# linistep1mod.net
KiCad netlist of a schematic drawn in EAGLE
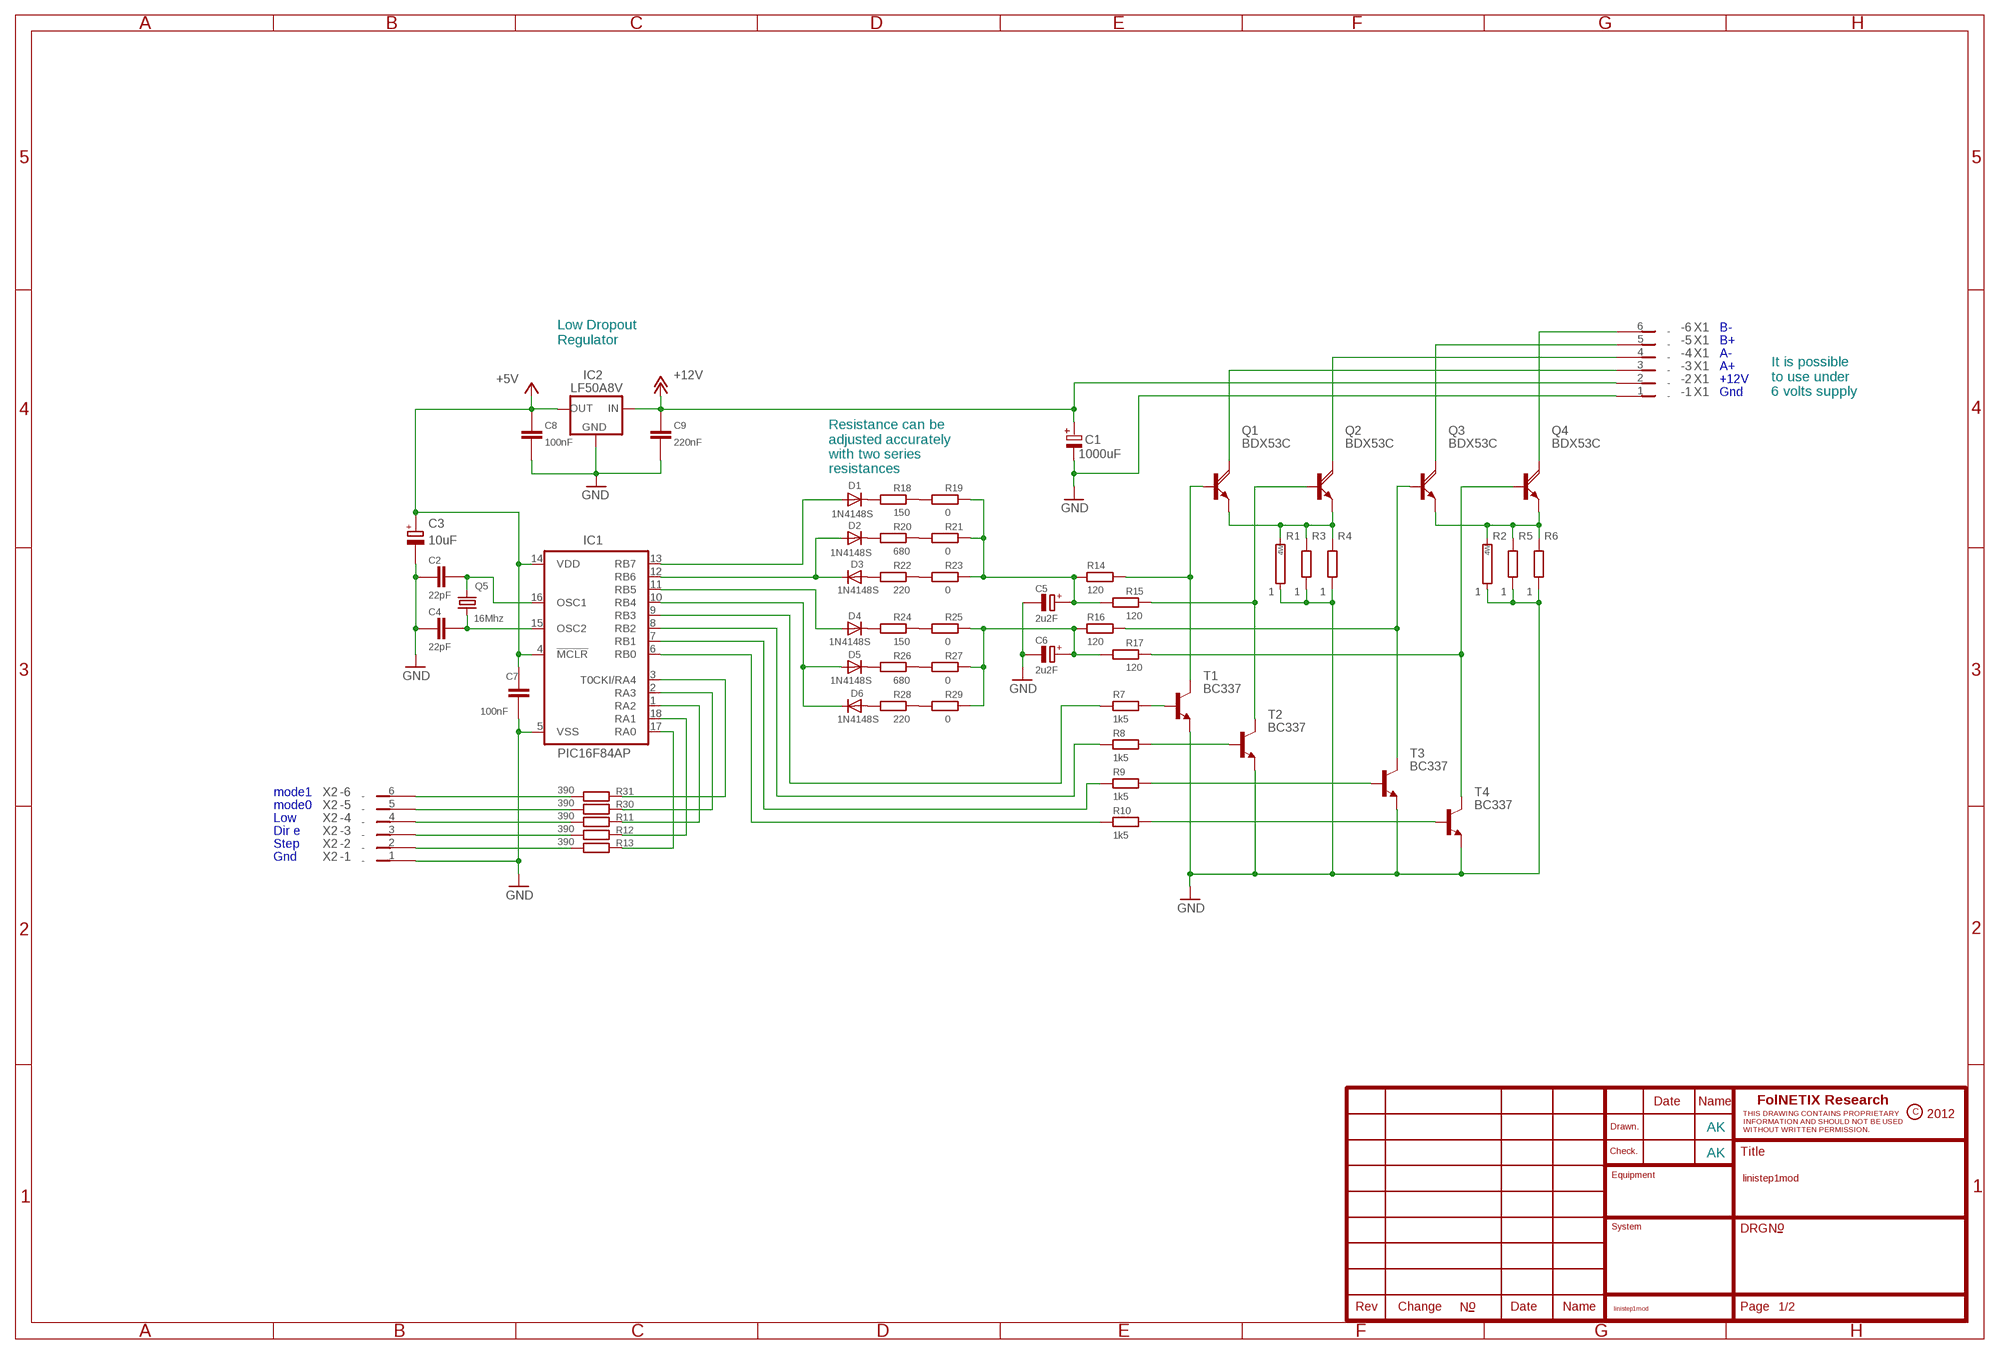
[diagram p0: schematic, sheet 1]
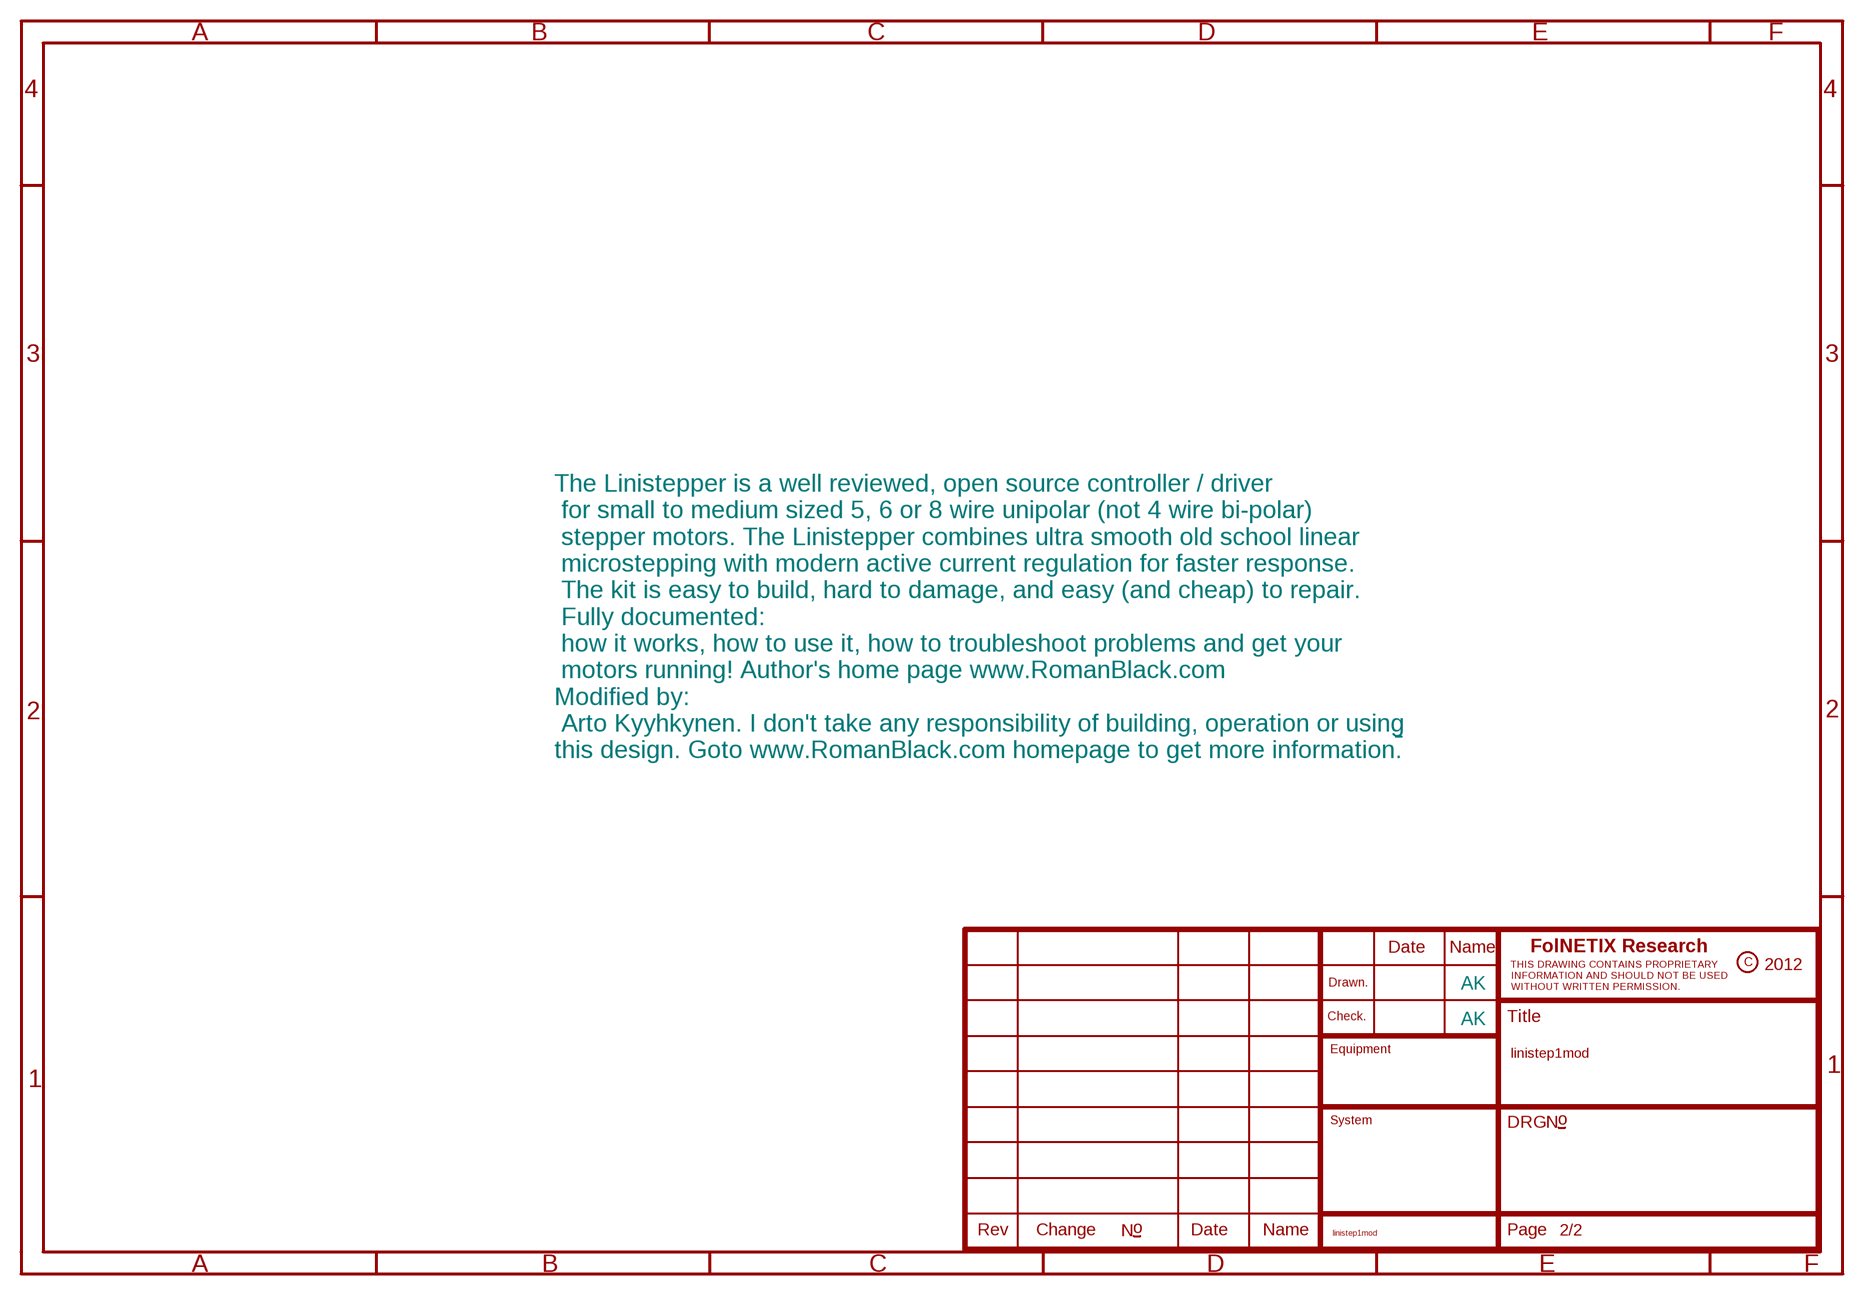
[diagram p1: schematic, sheet 2]

(export (version "E")
  (design (tool "Eeschema 10.0.6"))
  (components
    (comp (ref "C1")
      (value "1000uF")
      (footprint "eagle-import:E5-10,5")
      (libsource (lib "eagle-import") (part "E5-10,5"))
    )
    (comp (ref "C2")
      (value "22pF")
      (footprint "eagle-import:CAPC2012X145AN")
      (libsource (lib "eagle-import") (part "CAPACITOR_0805"))
    )
    (comp (ref "C3")
      (value "10uF")
      (footprint "eagle-import:CAPMP3528X210N")
      (libsource (lib "eagle-import") (part "POLARISED_B_CASE"))
    )
    (comp (ref "C4")
      (value "22pF")
      (footprint "eagle-import:CAPC2012X145AN")
      (libsource (lib "eagle-import") (part "CAPACITOR_0805"))
    )
    (comp (ref "C5")
      (value "2u2F")
      (footprint "eagle-import:CAPMP3216X180N")
      (libsource (lib "eagle-import") (part "POLARISED_A_CASE"))
    )
    (comp (ref "C6")
      (value "2u2F")
      (footprint "eagle-import:CAPMP3216X180N")
      (libsource (lib "eagle-import") (part "POLARISED_A_CASE"))
    )
    (comp (ref "C7")
      (value "100nF")
      (footprint "eagle-import:CAPC2012X145AN")
      (libsource (lib "eagle-import") (part "CAPACITOR_0805"))
    )
    (comp (ref "C8")
      (value "100nF")
      (footprint "eagle-import:CAPC2012X145AN")
      (libsource (lib "eagle-import") (part "CAPACITOR_0805"))
    )
    (comp (ref "C9")
      (value "220nF")
      (footprint "eagle-import:CAPC3225X168N")
      (libsource (lib "eagle-import") (part "CAPACITOR_1210"))
    )
    (comp (ref "D1")
      (value "1N4148S")
      (footprint "eagle-import:DO35-7A")
      (libsource (lib "eagle-import") (part "1N4148S"))
    )
    (comp (ref "D2")
      (value "1N4148S")
      (footprint "eagle-import:DO35-7A")
      (libsource (lib "eagle-import") (part "1N4148S"))
    )
    (comp (ref "D3")
      (value "1N4148S")
      (footprint "eagle-import:DO35-7A")
      (libsource (lib "eagle-import") (part "1N4148S"))
    )
    (comp (ref "D4")
      (value "1N4148S")
      (footprint "eagle-import:DO35-7A")
      (libsource (lib "eagle-import") (part "1N4148S"))
    )
    (comp (ref "D5")
      (value "1N4148S")
      (footprint "eagle-import:DO35-7A")
      (libsource (lib "eagle-import") (part "1N4148S"))
    )
    (comp (ref "D6")
      (value "1N4148S")
      (footprint "eagle-import:DO35-7A")
      (libsource (lib "eagle-import") (part "1N4148S"))
    )
    (comp (ref "IC1")
      (value "PIC16F84AP")
      (footprint "eagle-import:DIL18")
      (libsource (lib "eagle-import") (part "PIC16F8P4A"))
    )
    (comp (ref "IC2")
      (value "LF50A8V")
      (footprint "eagle-import:78XXL")
      (libsource (lib "eagle-import") (part "78XXL"))
    )
    (comp (ref "Q1")
      (value "BDX53C")
      (footprint "eagle-import:TO220AHS")
      (libsource (lib "eagle-import") (part "TIP120S"))
    )
    (comp (ref "Q2")
      (value "BDX53C")
      (footprint "eagle-import:TO220AHS")
      (libsource (lib "eagle-import") (part "TIP120S"))
    )
    (comp (ref "Q3")
      (value "BDX53C")
      (footprint "eagle-import:TO220AHS")
      (libsource (lib "eagle-import") (part "TIP120S"))
    )
    (comp (ref "Q4")
      (value "BDX53C")
      (footprint "eagle-import:TO220AHS")
      (libsource (lib "eagle-import") (part "TIP120S"))
    )
    (comp (ref "Q5")
      (value "16Mhz")
      (footprint "eagle-import:HC49_S")
      (libsource (lib "eagle-import") (part "HC49/S"))
    )
    (comp (ref "R1")
      (value "1")
      (footprint "eagle-import:206A")
      (libsource (lib "eagle-import") (part "206A"))
    )
    (comp (ref "R2")
      (value "1")
      (footprint "eagle-import:206A")
      (libsource (lib "eagle-import") (part "206A"))
    )
    (comp (ref "R3")
      (value "1")
      (footprint "eagle-import:0411_12")
      (libsource (lib "eagle-import") (part "0411/12"))
    )
    (comp (ref "R4")
      (value "1")
      (footprint "eagle-import:0411_12")
      (libsource (lib "eagle-import") (part "0411/12"))
    )
    (comp (ref "R5")
      (value "1")
      (footprint "eagle-import:0411_12")
      (libsource (lib "eagle-import") (part "0411/12"))
    )
    (comp (ref "R6")
      (value "1")
      (footprint "eagle-import:0411_12")
      (libsource (lib "eagle-import") (part "0411/12"))
    )
    (comp (ref "R7")
      (value "1k5")
      (footprint "eagle-import:RESC3115X70N")
      (libsource (lib "eagle-import") (part "RESISTOR_1206"))
    )
    (comp (ref "R8")
      (value "1k5")
      (footprint "eagle-import:RESC3115X70N")
      (libsource (lib "eagle-import") (part "RESISTOR_1206"))
    )
    (comp (ref "R9")
      (value "1k5")
      (footprint "eagle-import:RESC3115X70N")
      (libsource (lib "eagle-import") (part "RESISTOR_1206"))
    )
    (comp (ref "R10")
      (value "1k5")
      (footprint "eagle-import:RESC3115X70N")
      (libsource (lib "eagle-import") (part "RESISTOR_1206"))
    )
    (comp (ref "R11")
      (value "390")
      (footprint "eagle-import:RESC3115X70N")
      (libsource (lib "eagle-import") (part "RESISTOR_1206"))
    )
    (comp (ref "R12")
      (value "390")
      (footprint "eagle-import:RESC3115X70N")
      (libsource (lib "eagle-import") (part "RESISTOR_1206"))
    )
    (comp (ref "R13")
      (value "390")
      (footprint "eagle-import:RESC3115X70N")
      (libsource (lib "eagle-import") (part "RESISTOR_1206"))
    )
    (comp (ref "R14")
      (value "120")
      (footprint "eagle-import:RESC3115X70N")
      (libsource (lib "eagle-import") (part "RESISTOR_1206"))
    )
    (comp (ref "R15")
      (value "120")
      (footprint "eagle-import:RESC3115X70N")
      (libsource (lib "eagle-import") (part "RESISTOR_1206"))
    )
    (comp (ref "R16")
      (value "120")
      (footprint "eagle-import:RESC3115X70N")
      (libsource (lib "eagle-import") (part "RESISTOR_1206"))
    )
    (comp (ref "R17")
      (value "120")
      (footprint "eagle-import:RESC3115X70N")
      (libsource (lib "eagle-import") (part "RESISTOR_1206"))
    )
    (comp (ref "R18")
      (value "150")
      (footprint "eagle-import:RESC3115X70N")
      (libsource (lib "eagle-import") (part "RESISTOR_1206"))
    )
    (comp (ref "R19")
      (value "0")
      (footprint "eagle-import:RESC3115X70N")
      (libsource (lib "eagle-import") (part "RESISTOR_1206"))
    )
    (comp (ref "R20")
      (value "680")
      (footprint "eagle-import:RESC3115X70N")
      (libsource (lib "eagle-import") (part "RESISTOR_1206"))
    )
    (comp (ref "R21")
      (value "0")
      (footprint "eagle-import:RESC3115X70N")
      (libsource (lib "eagle-import") (part "RESISTOR_1206"))
    )
    (comp (ref "R22")
      (value "220")
      (footprint "eagle-import:RESC3115X70N")
      (libsource (lib "eagle-import") (part "RESISTOR_1206"))
    )
    (comp (ref "R23")
      (value "0")
      (footprint "eagle-import:RESC3115X70N")
      (libsource (lib "eagle-import") (part "RESISTOR_1206"))
    )
    (comp (ref "R24")
      (value "150")
      (footprint "eagle-import:RESC3115X70N")
      (libsource (lib "eagle-import") (part "RESISTOR_1206"))
    )
    (comp (ref "R25")
      (value "0")
      (footprint "eagle-import:RESC3115X70N")
      (libsource (lib "eagle-import") (part "RESISTOR_1206"))
    )
    (comp (ref "R26")
      (value "680")
      (footprint "eagle-import:RESC3115X70N")
      (libsource (lib "eagle-import") (part "RESISTOR_1206"))
    )
    (comp (ref "R27")
      (value "0")
      (footprint "eagle-import:RESC3115X70N")
      (libsource (lib "eagle-import") (part "RESISTOR_1206"))
    )
    (comp (ref "R28")
      (value "220")
      (footprint "eagle-import:RESC3115X70N")
      (libsource (lib "eagle-import") (part "RESISTOR_1206"))
    )
    (comp (ref "R29")
      (value "0")
      (footprint "eagle-import:RESC3115X70N")
      (libsource (lib "eagle-import") (part "RESISTOR_1206"))
    )
    (comp (ref "R30")
      (value "390")
      (footprint "eagle-import:RESC3115X70N")
      (libsource (lib "eagle-import") (part "RESISTOR_1206"))
    )
    (comp (ref "R31")
      (value "390")
      (footprint "eagle-import:RESC3115X70N")
      (libsource (lib "eagle-import") (part "RESISTOR_1206"))
    )
    (comp (ref "T1")
      (value "BC337")
      (footprint "eagle-import:TO92")
      (libsource (lib "eagle-import") (part "BC337"))
    )
    (comp (ref "T2")
      (value "BC337")
      (footprint "eagle-import:TO92")
      (libsource (lib "eagle-import") (part "BC337"))
    )
    (comp (ref "T3")
      (value "BC337")
      (footprint "eagle-import:TO92")
      (libsource (lib "eagle-import") (part "BC337"))
    )
    (comp (ref "T4")
      (value "BC337")
      (footprint "eagle-import:TO92")
      (libsource (lib "eagle-import") (part "BC337"))
    )
    (comp (ref "X1")
      (value "RIACON-6")
      (footprint "eagle-import:RIACON-6")
      (libsource (lib "eagle-import") (part "RIACON-6"))
    )
    (comp (ref "X2")
      (value "RIACON-6")
      (footprint "eagle-import:RIACON-6")
      (libsource (lib "eagle-import") (part "RIACON-6"))
    )
  )
  (nets
    (net (code "1") (name "+5V") (class "Default")
      (node (ref "C3") (pin "+") (pinfunction "+_+") (pintype "passive"))
      (node (ref "C7") (pin "2") (pinfunction "2_2") (pintype "passive"))
      (node (ref "C8") (pin "2") (pinfunction "2_2") (pintype "passive"))
      (node (ref "IC1") (pin "14") (pinfunction "VDD_14") (pintype "power_in"))
      (node (ref "IC1") (pin "4") (pinfunction "~{MCLR}_4") (pintype "input"))
      (node (ref "IC2") (pin "OUT") (pinfunction "OUT_OUT") (pintype "passive"))
    )
    (net (code "2") (name "+12V") (class "Default")
      (node (ref "C1") (pin "+") (pinfunction "+_+") (pintype "passive"))
      (node (ref "C9") (pin "2") (pinfunction "2_2") (pintype "passive"))
      (node (ref "IC2") (pin "IN") (pinfunction "IN_IN") (pintype "input"))
      (node (ref "X1") (pin "2") (pinfunction "-_2") (pintype "passive"))
    )
    (net (code "3") (name "GND") (class "Default")
      (node (ref "C1") (pin "-") (pinfunction "-_-") (pintype "passive"))
      (node (ref "C2") (pin "1") (pinfunction "1_1") (pintype "passive"))
      (node (ref "C3") (pin "-") (pinfunction "-_-") (pintype "passive"))
      (node (ref "C4") (pin "1") (pinfunction "1_1") (pintype "passive"))
      (node (ref "C5") (pin "-") (pinfunction "-_-") (pintype "passive"))
      (node (ref "C6") (pin "-") (pinfunction "-_-") (pintype "passive"))
      (node (ref "C7") (pin "1") (pinfunction "1_1") (pintype "passive"))
      (node (ref "C8") (pin "1") (pinfunction "1_1") (pintype "passive"))
      (node (ref "C9") (pin "1") (pinfunction "1_1") (pintype "passive"))
      (node (ref "IC1") (pin "5") (pinfunction "VSS_5") (pintype "power_in"))
      (node (ref "IC2") (pin "GND") (pinfunction "GND_GND") (pintype "input"))
      (node (ref "R1") (pin "1") (pinfunction "1_1") (pintype "passive"))
      (node (ref "R2") (pin "1") (pinfunction "1_1") (pintype "passive"))
      (node (ref "R3") (pin "1") (pinfunction "1_1") (pintype "passive"))
      (node (ref "R4") (pin "1") (pinfunction "1_1") (pintype "passive"))
      (node (ref "R5") (pin "1") (pinfunction "1_1") (pintype "passive"))
      (node (ref "R6") (pin "1") (pinfunction "1_1") (pintype "passive"))
      (node (ref "T1") (pin "1") (pinfunction "E_1") (pintype "passive"))
      (node (ref "T2") (pin "1") (pinfunction "E_1") (pintype "passive"))
      (node (ref "T3") (pin "1") (pinfunction "E_1") (pintype "passive"))
      (node (ref "T4") (pin "1") (pinfunction "E_1") (pintype "passive"))
      (node (ref "X1") (pin "1") (pinfunction "-_1") (pintype "passive"))
      (node (ref "X2") (pin "1") (pinfunction "-_1") (pintype "passive"))
    )
    (net (code "4") (name "Net-(C5-Pad+)") (class "Default")
      (node (ref "C5") (pin "+") (pinfunction "+_+") (pintype "passive"))
      (node (ref "R14") (pin "1") (pinfunction "1_1") (pintype "passive"))
      (node (ref "R15") (pin "1") (pinfunction "1_1") (pintype "passive"))
      (node (ref "R19") (pin "2") (pinfunction "2_2") (pintype "passive"))
      (node (ref "R21") (pin "2") (pinfunction "2_2") (pintype "passive"))
      (node (ref "R23") (pin "2") (pinfunction "2_2") (pintype "passive"))
    )
    (net (code "5") (name "Net-(C6-Pad+)") (class "Default")
      (node (ref "C6") (pin "+") (pinfunction "+_+") (pintype "passive"))
      (node (ref "R16") (pin "1") (pinfunction "1_1") (pintype "passive"))
      (node (ref "R17") (pin "1") (pinfunction "1_1") (pintype "passive"))
      (node (ref "R25") (pin "2") (pinfunction "2_2") (pintype "passive"))
      (node (ref "R27") (pin "2") (pinfunction "2_2") (pintype "passive"))
      (node (ref "R29") (pin "2") (pinfunction "2_2") (pintype "passive"))
    )
    (net (code "6") (name "Net-(D1-PadC)") (class "Default")
      (node (ref "D1") (pin "C") (pinfunction "C_C") (pintype "passive"))
      (node (ref "R18") (pin "1") (pinfunction "1_1") (pintype "passive"))
    )
    (net (code "7") (name "Net-(D2-PadC)") (class "Default")
      (node (ref "D2") (pin "C") (pinfunction "C_C") (pintype "passive"))
      (node (ref "R20") (pin "1") (pinfunction "1_1") (pintype "passive"))
    )
    (net (code "8") (name "Net-(D3-PadA)") (class "Default")
      (node (ref "D3") (pin "A") (pinfunction "A_A") (pintype "passive"))
      (node (ref "R22") (pin "1") (pinfunction "1_1") (pintype "passive"))
    )
    (net (code "9") (name "Net-(D4-PadC)") (class "Default")
      (node (ref "D4") (pin "C") (pinfunction "C_C") (pintype "passive"))
      (node (ref "R24") (pin "1") (pinfunction "1_1") (pintype "passive"))
    )
    (net (code "10") (name "Net-(D5-PadC)") (class "Default")
      (node (ref "D5") (pin "C") (pinfunction "C_C") (pintype "passive"))
      (node (ref "R26") (pin "1") (pinfunction "1_1") (pintype "passive"))
    )
    (net (code "11") (name "Net-(D6-PadA)") (class "Default")
      (node (ref "D6") (pin "A") (pinfunction "A_A") (pintype "passive"))
      (node (ref "R28") (pin "1") (pinfunction "1_1") (pintype "passive"))
    )
    (net (code "12") (name "Net-(IC1-OSC1)") (class "Default")
      (node (ref "C2") (pin "2") (pinfunction "2_2") (pintype "passive"))
      (node (ref "IC1") (pin "16") (pinfunction "OSC1_16") (pintype "input"))
      (node (ref "Q5") (pin "2") (pinfunction "2_2") (pintype "passive"))
    )
    (net (code "13") (name "Net-(IC1-OSC2)") (class "Default")
      (node (ref "C4") (pin "2") (pinfunction "2_2") (pintype "passive"))
      (node (ref "IC1") (pin "15") (pinfunction "OSC2_15") (pintype "output"))
      (node (ref "Q5") (pin "1") (pinfunction "1_1") (pintype "passive"))
    )
    (net (code "14") (name "Net-(IC1-RA0)") (class "Default")
      (node (ref "IC1") (pin "17") (pinfunction "RA0_17") (pintype "bidirectional"))
      (node (ref "R13") (pin "2") (pinfunction "2_2") (pintype "passive"))
    )
    (net (code "15") (name "Net-(IC1-RA1)") (class "Default")
      (node (ref "IC1") (pin "18") (pinfunction "RA1_18") (pintype "bidirectional"))
      (node (ref "R12") (pin "2") (pinfunction "2_2") (pintype "passive"))
    )
    (net (code "16") (name "Net-(IC1-RA2)") (class "Default")
      (node (ref "IC1") (pin "1") (pinfunction "RA2_1") (pintype "bidirectional"))
      (node (ref "R11") (pin "2") (pinfunction "2_2") (pintype "passive"))
    )
    (net (code "17") (name "Net-(IC1-RA3)") (class "Default")
      (node (ref "IC1") (pin "2") (pinfunction "RA3_2") (pintype "bidirectional"))
      (node (ref "R30") (pin "2") (pinfunction "2_2") (pintype "passive"))
    )
    (net (code "18") (name "Net-(IC1-RB0)") (class "Default")
      (node (ref "IC1") (pin "6") (pinfunction "RB0_6") (pintype "bidirectional"))
      (node (ref "R10") (pin "1") (pinfunction "1_1") (pintype "passive"))
    )
    (net (code "19") (name "Net-(IC1-RB1)") (class "Default")
      (node (ref "IC1") (pin "7") (pinfunction "RB1_7") (pintype "bidirectional"))
      (node (ref "R9") (pin "1") (pinfunction "1_1") (pintype "passive"))
    )
    (net (code "20") (name "Net-(IC1-RB2)") (class "Default")
      (node (ref "IC1") (pin "8") (pinfunction "RB2_8") (pintype "bidirectional"))
      (node (ref "R8") (pin "1") (pinfunction "1_1") (pintype "passive"))
    )
    (net (code "21") (name "Net-(IC1-RB3)") (class "Default")
      (node (ref "IC1") (pin "9") (pinfunction "RB3_9") (pintype "bidirectional"))
      (node (ref "R7") (pin "1") (pinfunction "1_1") (pintype "passive"))
    )
    (net (code "22") (name "Net-(IC1-RB4)") (class "Default")
      (node (ref "D5") (pin "A") (pinfunction "A_A") (pintype "passive"))
      (node (ref "D6") (pin "C") (pinfunction "C_C") (pintype "passive"))
      (node (ref "IC1") (pin "10") (pinfunction "RB4_10") (pintype "bidirectional"))
    )
    (net (code "23") (name "Net-(IC1-RB5)") (class "Default")
      (node (ref "D4") (pin "A") (pinfunction "A_A") (pintype "passive"))
      (node (ref "IC1") (pin "11") (pinfunction "RB5_11") (pintype "bidirectional"))
    )
    (net (code "24") (name "Net-(IC1-RB6)") (class "Default")
      (node (ref "D2") (pin "A") (pinfunction "A_A") (pintype "passive"))
      (node (ref "D3") (pin "C") (pinfunction "C_C") (pintype "passive"))
      (node (ref "IC1") (pin "12") (pinfunction "RB6_12") (pintype "bidirectional"))
    )
    (net (code "25") (name "Net-(IC1-RB7)") (class "Default")
      (node (ref "D1") (pin "A") (pinfunction "A_A") (pintype "passive"))
      (node (ref "IC1") (pin "13") (pinfunction "RB7_13") (pintype "bidirectional"))
    )
    (net (code "26") (name "Net-(IC1-T0CKI{slash}RA4)") (class "Default")
      (node (ref "IC1") (pin "3") (pinfunction "T0CKI/RA4_3") (pintype "bidirectional"))
      (node (ref "R31") (pin "2") (pinfunction "2_2") (pintype "passive"))
    )
    (net (code "27") (name "Net-(Q1-PadE)") (class "Default")
      (node (ref "Q1") (pin "E") (pinfunction "E_E") (pintype "passive"))
      (node (ref "Q2") (pin "E") (pinfunction "E_E") (pintype "passive"))
      (node (ref "R1") (pin "2") (pinfunction "2_2") (pintype "passive"))
      (node (ref "R3") (pin "2") (pinfunction "2_2") (pintype "passive"))
      (node (ref "R4") (pin "2") (pinfunction "2_2") (pintype "passive"))
    )
    (net (code "28") (name "Net-(Q3-PadE)") (class "Default")
      (node (ref "Q3") (pin "E") (pinfunction "E_E") (pintype "passive"))
      (node (ref "Q4") (pin "E") (pinfunction "E_E") (pintype "passive"))
      (node (ref "R2") (pin "2") (pinfunction "2_2") (pintype "passive"))
      (node (ref "R5") (pin "2") (pinfunction "2_2") (pintype "passive"))
      (node (ref "R6") (pin "2") (pinfunction "2_2") (pintype "passive"))
    )
    (net (code "29") (name "Net-(R18-Pad2)") (class "Default")
      (node (ref "R18") (pin "2") (pinfunction "2_2") (pintype "passive"))
      (node (ref "R19") (pin "1") (pinfunction "1_1") (pintype "passive"))
    )
    (net (code "30") (name "Net-(R20-Pad2)") (class "Default")
      (node (ref "R20") (pin "2") (pinfunction "2_2") (pintype "passive"))
      (node (ref "R21") (pin "1") (pinfunction "1_1") (pintype "passive"))
    )
    (net (code "31") (name "Net-(R22-Pad2)") (class "Default")
      (node (ref "R22") (pin "2") (pinfunction "2_2") (pintype "passive"))
      (node (ref "R23") (pin "1") (pinfunction "1_1") (pintype "passive"))
    )
    (net (code "32") (name "Net-(R24-Pad2)") (class "Default")
      (node (ref "R24") (pin "2") (pinfunction "2_2") (pintype "passive"))
      (node (ref "R25") (pin "1") (pinfunction "1_1") (pintype "passive"))
    )
    (net (code "33") (name "Net-(R26-Pad2)") (class "Default")
      (node (ref "R26") (pin "2") (pinfunction "2_2") (pintype "passive"))
      (node (ref "R27") (pin "1") (pinfunction "1_1") (pintype "passive"))
    )
    (net (code "34") (name "Net-(R28-Pad2)") (class "Default")
      (node (ref "R28") (pin "2") (pinfunction "2_2") (pintype "passive"))
      (node (ref "R29") (pin "1") (pinfunction "1_1") (pintype "passive"))
    )
    (net (code "35") (name "Net-(T1-B)") (class "Default")
      (node (ref "R7") (pin "2") (pinfunction "2_2") (pintype "passive"))
      (node (ref "T1") (pin "2") (pinfunction "B_2") (pintype "passive"))
    )
    (net (code "36") (name "Net-(T1-C)") (class "Default")
      (node (ref "Q1") (pin "B") (pinfunction "B_B") (pintype "passive"))
      (node (ref "R14") (pin "2") (pinfunction "2_2") (pintype "passive"))
      (node (ref "T1") (pin "3") (pinfunction "C_3") (pintype "passive"))
    )
    (net (code "37") (name "Net-(T2-B)") (class "Default")
      (node (ref "R8") (pin "2") (pinfunction "2_2") (pintype "passive"))
      (node (ref "T2") (pin "2") (pinfunction "B_2") (pintype "passive"))
    )
    (net (code "38") (name "Net-(T2-C)") (class "Default")
      (node (ref "Q2") (pin "B") (pinfunction "B_B") (pintype "passive"))
      (node (ref "R15") (pin "2") (pinfunction "2_2") (pintype "passive"))
      (node (ref "T2") (pin "3") (pinfunction "C_3") (pintype "passive"))
    )
    (net (code "39") (name "Net-(T3-B)") (class "Default")
      (node (ref "R9") (pin "2") (pinfunction "2_2") (pintype "passive"))
      (node (ref "T3") (pin "2") (pinfunction "B_2") (pintype "passive"))
    )
    (net (code "40") (name "Net-(T3-C)") (class "Default")
      (node (ref "Q3") (pin "B") (pinfunction "B_B") (pintype "passive"))
      (node (ref "R16") (pin "2") (pinfunction "2_2") (pintype "passive"))
      (node (ref "T3") (pin "3") (pinfunction "C_3") (pintype "passive"))
    )
    (net (code "41") (name "Net-(T4-B)") (class "Default")
      (node (ref "R10") (pin "2") (pinfunction "2_2") (pintype "passive"))
      (node (ref "T4") (pin "2") (pinfunction "B_2") (pintype "passive"))
    )
    (net (code "42") (name "Net-(T4-C)") (class "Default")
      (node (ref "Q4") (pin "B") (pinfunction "B_B") (pintype "passive"))
      (node (ref "R17") (pin "2") (pinfunction "2_2") (pintype "passive"))
      (node (ref "T4") (pin "3") (pinfunction "C_3") (pintype "passive"))
    )
    (net (code "43") (name "Net-(X1C--)") (class "Default")
      (node (ref "Q1") (pin "C") (pinfunction "C_C") (pintype "passive"))
      (node (ref "X1") (pin "3") (pinfunction "-_3") (pintype "passive"))
    )
    (net (code "44") (name "Net-(X1D--)") (class "Default")
      (node (ref "Q2") (pin "C") (pinfunction "C_C") (pintype "passive"))
      (node (ref "X1") (pin "4") (pinfunction "-_4") (pintype "passive"))
    )
    (net (code "45") (name "Net-(X1E--)") (class "Default")
      (node (ref "Q3") (pin "C") (pinfunction "C_C") (pintype "passive"))
      (node (ref "X1") (pin "5") (pinfunction "-_5") (pintype "passive"))
    )
    (net (code "46") (name "Net-(X1F--)") (class "Default")
      (node (ref "Q4") (pin "C") (pinfunction "C_C") (pintype "passive"))
      (node (ref "X1") (pin "6") (pinfunction "-_6") (pintype "passive"))
    )
    (net (code "47") (name "Net-(X2B--)") (class "Default")
      (node (ref "R13") (pin "1") (pinfunction "1_1") (pintype "passive"))
      (node (ref "X2") (pin "2") (pinfunction "-_2") (pintype "passive"))
    )
    (net (code "48") (name "Net-(X2C--)") (class "Default")
      (node (ref "R12") (pin "1") (pinfunction "1_1") (pintype "passive"))
      (node (ref "X2") (pin "3") (pinfunction "-_3") (pintype "passive"))
    )
    (net (code "49") (name "Net-(X2D--)") (class "Default")
      (node (ref "R11") (pin "1") (pinfunction "1_1") (pintype "passive"))
      (node (ref "X2") (pin "4") (pinfunction "-_4") (pintype "passive"))
    )
    (net (code "50") (name "Net-(X2E--)") (class "Default")
      (node (ref "R30") (pin "1") (pinfunction "1_1") (pintype "passive"))
      (node (ref "X2") (pin "5") (pinfunction "-_5") (pintype "passive"))
    )
    (net (code "51") (name "Net-(X2F--)") (class "Default")
      (node (ref "R31") (pin "1") (pinfunction "1_1") (pintype "passive"))
      (node (ref "X2") (pin "6") (pinfunction "-_6") (pintype "passive"))
    )
  )
)
